# weather-cube_sensor_hdc1080_sht31d_ntc.net
KiCad netlist of a schematic drawn in EAGLE
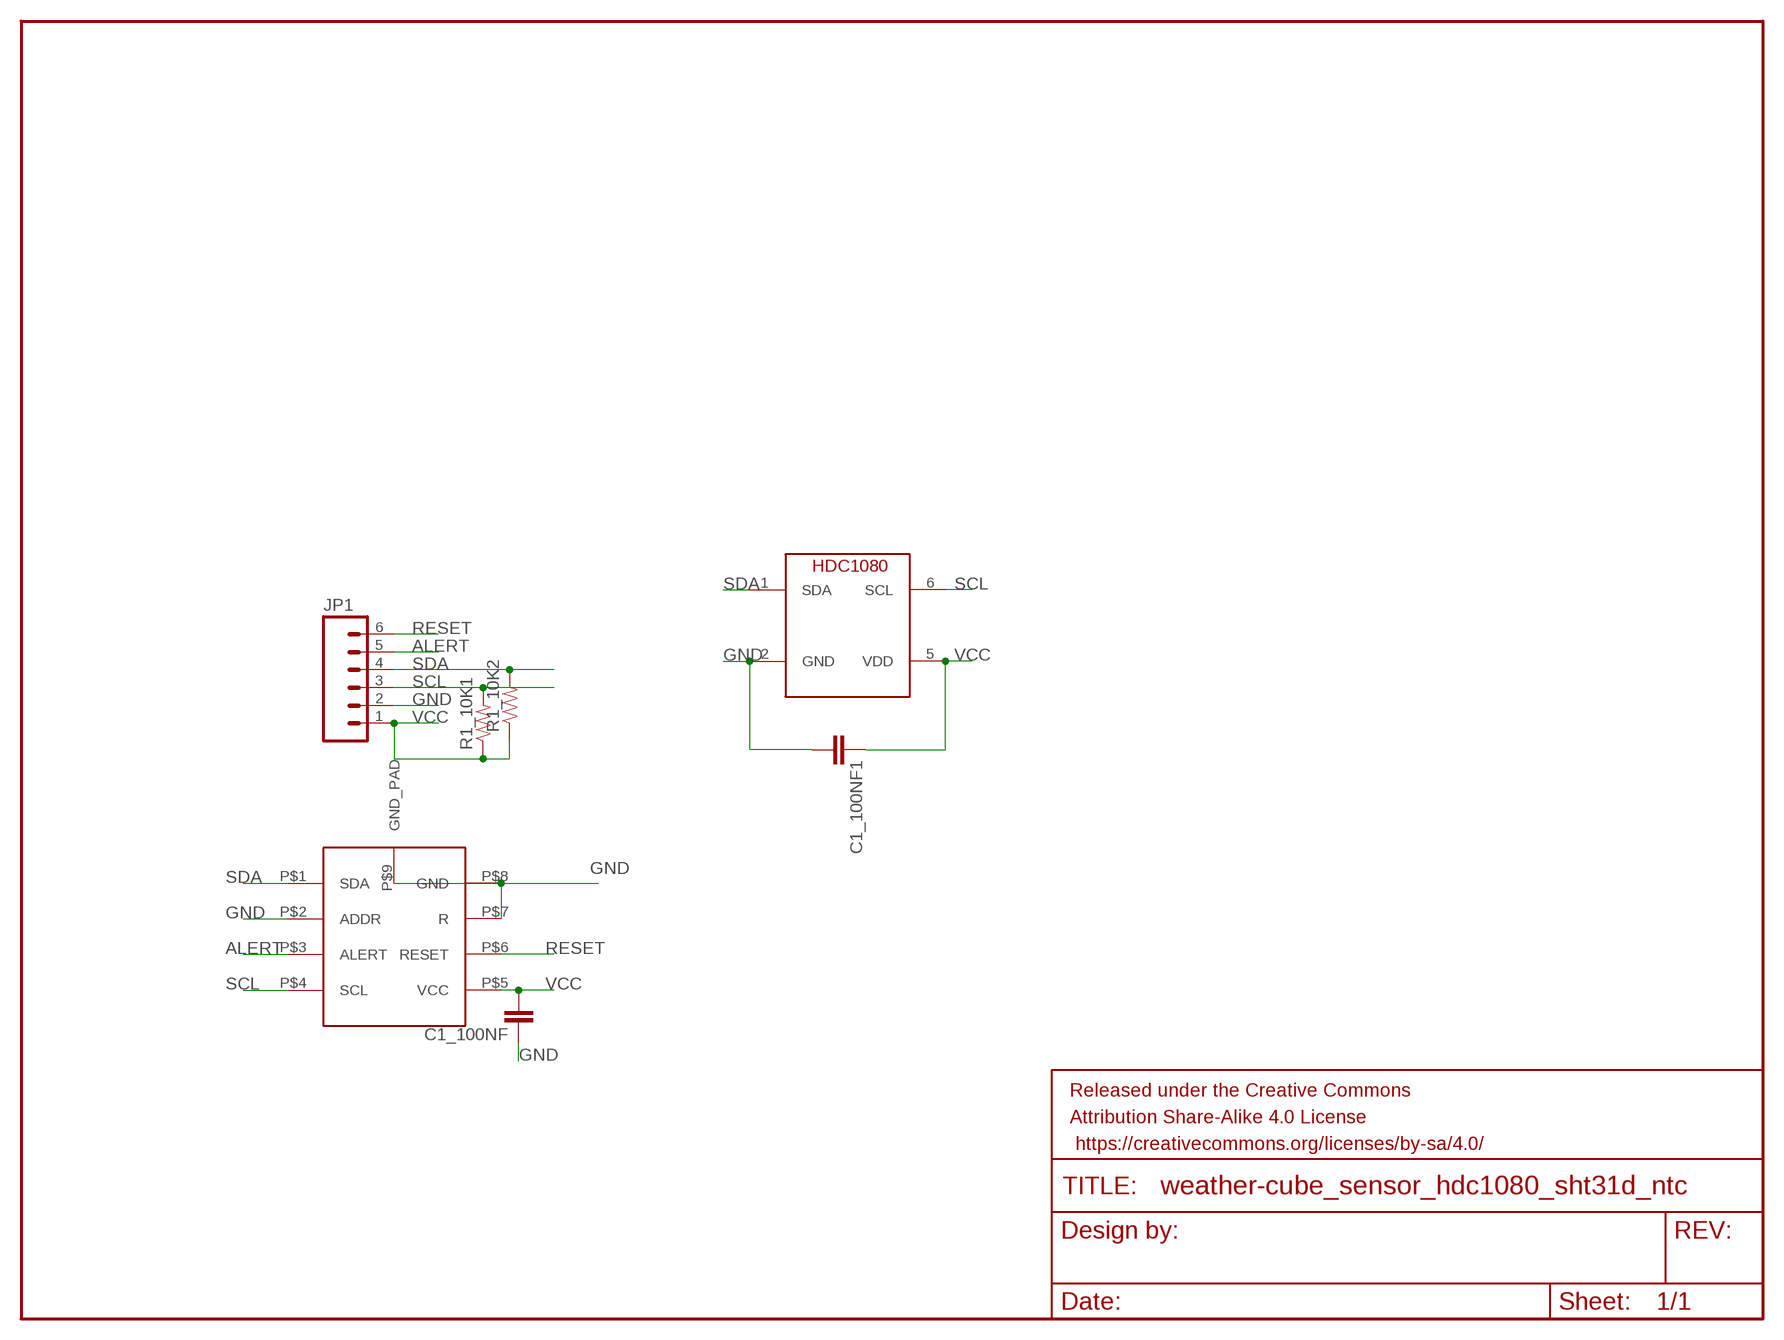
[diagram p0: schematic, sheet 1]

(export (version "E")
  (design (tool "Eeschema 10.0.6"))
  (components
    (comp (ref "C1_100NF")
      (value "CAP0603-CAP")
      (footprint "eagle-import:0603-CAP")
      (libsource (lib "eagle-import") (part "CAP0603-CAP"))
    )
    (comp (ref "C1_100NF1")
      (value "CAP0603-CAP")
      (footprint "eagle-import:0603-CAP")
      (libsource (lib "eagle-import") (part "CAP0603-CAP"))
    )
    (comp (ref "FRAME1")
      (value "FRAME-LETTER")
      (footprint "eagle-import:CREATIVE_COMMONS")
      (libsource (lib "eagle-import") (part "FRAME-LETTER"))
    )
    (comp (ref "JP1")
      (value "M06SILK_FEMALE_PTH")
      (footprint "eagle-import:1X06")
      (libsource (lib "eagle-import") (part "M06SILK_FEMALE_PTH"))
    )
    (comp (ref "R1_10K1")
      (value "RESISTOR0603-RES")
      (footprint "eagle-import:0603-RES")
      (libsource (lib "eagle-import") (part "RESISTOR0603-RES"))
    )
    (comp (ref "R1_10K2")
      (value "RESISTOR0603-RES")
      (footprint "eagle-import:0603-RES")
      (libsource (lib "eagle-import") (part "RESISTOR0603-RES"))
    )
    (comp (ref "U$1")
      (value "SHT31-D")
      (footprint "eagle-import:SHT31-D")
      (libsource (lib "eagle-import") (part "SHT31-D"))
    )
    (comp (ref "U$2")
      (value "HDC1080")
      (footprint "eagle-import:WSON-6-PAD")
      (libsource (lib "eagle-import") (part "HDC1080"))
    )
  )
  (nets
    (net (code "1") (name "/ALERT") (class "Default")
      (node (ref "JP1") (pin "5") (pinfunction "5_5") (pintype "passive"))
      (node (ref "U$1") (pin "P$3") (pinfunction "ALERT_P$3") (pintype "bidirectional"))
    )
    (net (code "2") (name "/GND") (class "Default")
      (node (ref "C1_100NF") (pin "1") (pinfunction "1_1") (pintype "passive"))
      (node (ref "C1_100NF1") (pin "2") (pinfunction "2_2") (pintype "passive"))
      (node (ref "JP1") (pin "2") (pinfunction "2_2") (pintype "passive"))
      (node (ref "U$1") (pin "P$2") (pinfunction "ADDR_P$2") (pintype "bidirectional"))
      (node (ref "U$1") (pin "P$7") (pinfunction "R_P$7") (pintype "bidirectional"))
      (node (ref "U$1") (pin "P$8") (pinfunction "GND_P$8") (pintype "bidirectional"))
      (node (ref "U$1") (pin "P$9") (pinfunction "GND_PAD_P$9") (pintype "bidirectional"))
      (node (ref "U$2") (pin "2") (pinfunction "GND_2") (pintype "bidirectional"))
    )
    (net (code "3") (name "/RESET") (class "Default")
      (node (ref "JP1") (pin "6") (pinfunction "6_6") (pintype "passive"))
      (node (ref "U$1") (pin "P$6") (pinfunction "RESET_P$6") (pintype "bidirectional"))
    )
    (net (code "4") (name "/SCL") (class "Default")
      (node (ref "JP1") (pin "3") (pinfunction "3_3") (pintype "passive"))
      (node (ref "R1_10K1") (pin "2") (pinfunction "2_2") (pintype "passive"))
      (node (ref "U$1") (pin "P$4") (pinfunction "SCL_P$4") (pintype "bidirectional"))
      (node (ref "U$2") (pin "6") (pinfunction "SCL_6") (pintype "bidirectional"))
    )
    (net (code "5") (name "/SDA") (class "Default")
      (node (ref "JP1") (pin "4") (pinfunction "4_4") (pintype "passive"))
      (node (ref "R1_10K2") (pin "2") (pinfunction "2_2") (pintype "passive"))
      (node (ref "U$1") (pin "P$1") (pinfunction "SDA_P$1") (pintype "bidirectional"))
      (node (ref "U$2") (pin "1") (pinfunction "SDA_1") (pintype "bidirectional"))
    )
    (net (code "6") (name "/VCC") (class "Default")
      (node (ref "C1_100NF") (pin "2") (pinfunction "2_2") (pintype "passive"))
      (node (ref "C1_100NF1") (pin "1") (pinfunction "1_1") (pintype "passive"))
      (node (ref "JP1") (pin "1") (pinfunction "1_1") (pintype "passive"))
      (node (ref "R1_10K1") (pin "1") (pinfunction "1_1") (pintype "passive"))
      (node (ref "R1_10K2") (pin "1") (pinfunction "1_1") (pintype "passive"))
      (node (ref "U$1") (pin "P$5") (pinfunction "VCC_P$5") (pintype "bidirectional"))
      (node (ref "U$2") (pin "5") (pinfunction "VDD_5") (pintype "bidirectional"))
    )
  )
)
